# V6_0.net
KiCad netlist of a schematic drawn in EAGLE
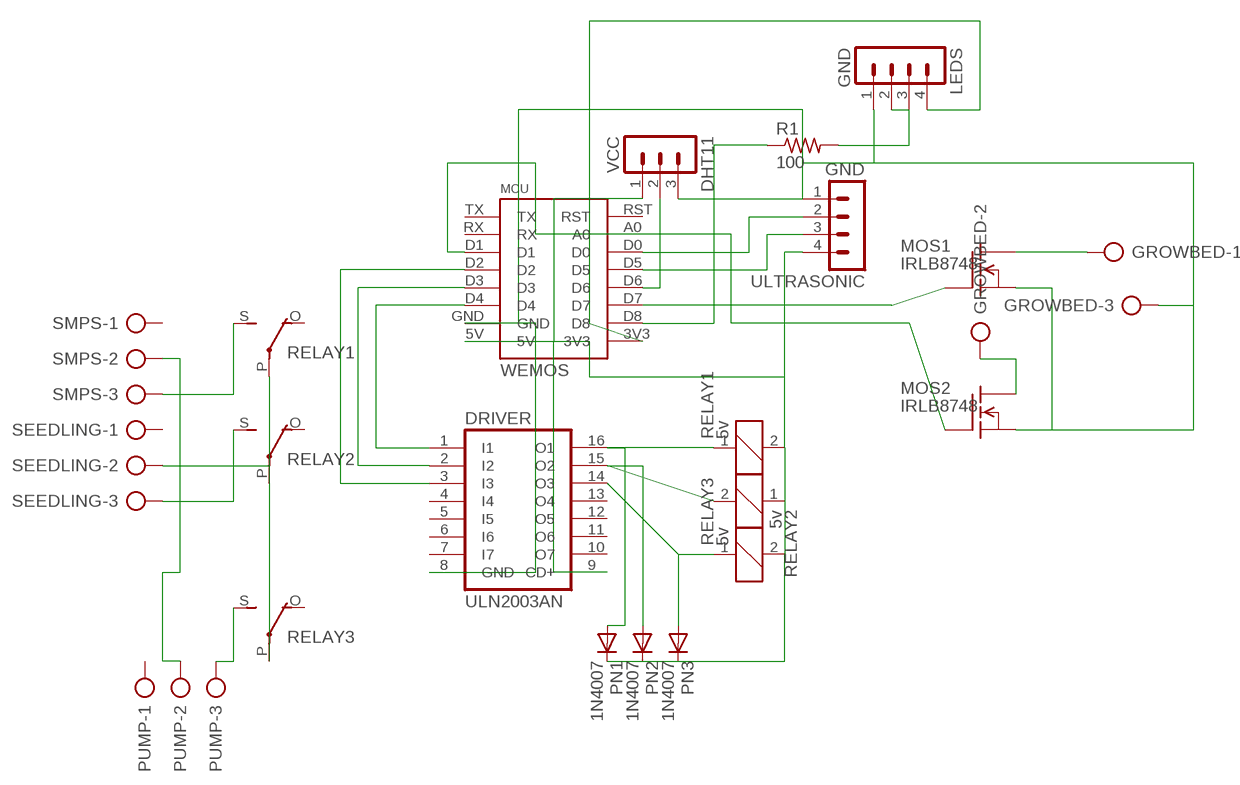
[diagram p0: schematic, sheet 1]

(export (version "E")
  (design (tool "Eeschema 10.0.6"))
  (components
    (comp (ref "DHT11")
      (value "VCC")
      (footprint "eagle-import:MA03-1")
      (libsource (lib "eagle-import") (part "MA03-1"))
    )
    (comp (ref "DRIVER")
      (value "ULN2003AN")
      (footprint "eagle-import:DIL16")
      (libsource (lib "eagle-import") (part "ULN2003AN"))
    )
    (comp (ref "GROWBED")
      (value "AK300/3")
      (footprint "eagle-import:AK300_3")
      (libsource (lib "eagle-import") (part "AK300/3"))
    )
    (comp (ref "LEDS")
      (value "GND")
      (footprint "eagle-import:MA04-1")
      (fields (field (name "OC_FARNELL") "unknown") (field (name "OC_NEWARK") "unknown"))
      (libsource (lib "eagle-import") (part "MA04-1"))
    )
    (comp (ref "MCU")
      (value "WEMOS")
      (footprint "eagle-import:WEMOS")
      (libsource (lib "eagle-import") (part "WEMOS"))
    )
    (comp (ref "MOS1")
      (value "IRLB8748")
      (footprint "eagle-import:TO220")
      (libsource (lib "eagle-import") (part "IRF540"))
    )
    (comp (ref "MOS2")
      (value "IRLB8748")
      (footprint "eagle-import:TO220")
      (libsource (lib "eagle-import") (part "IRF540"))
    )
    (comp (ref "PN1")
      (value "1N4007")
      (footprint "eagle-import:DO41-10")
      (libsource (lib "eagle-import") (part "1N4004"))
    )
    (comp (ref "PN2")
      (value "1N4007")
      (footprint "eagle-import:DO41-10")
      (libsource (lib "eagle-import") (part "1N4004"))
    )
    (comp (ref "PN3")
      (value "1N4007")
      (footprint "eagle-import:DO41-10")
      (libsource (lib "eagle-import") (part "1N4004"))
    )
    (comp (ref "PUMP")
      (value "AK300/3")
      (footprint "eagle-import:AK300_3")
      (libsource (lib "eagle-import") (part "AK300/3"))
    )
    (comp (ref "R1")
      (value "100")
      (footprint "eagle-import:0207_7")
      (libsource (lib "eagle-import") (part "R-US_0207/7"))
    )
    (comp (ref "RELAY1")
      (value "5v")
      (footprint "eagle-import:ZF112")
      (libsource (lib "eagle-import") (part "ZF112"))
    )
    (comp (ref "RELAY2")
      (value "5v")
      (footprint "eagle-import:ZF112")
      (libsource (lib "eagle-import") (part "ZF112"))
    )
    (comp (ref "RELAY3")
      (value "5v")
      (footprint "eagle-import:ZF112")
      (libsource (lib "eagle-import") (part "ZF112"))
    )
    (comp (ref "SEEDLING")
      (value "AK300/3")
      (footprint "eagle-import:AK300_3")
      (libsource (lib "eagle-import") (part "AK300/3"))
    )
    (comp (ref "SMPS")
      (value "AK300/3")
      (footprint "eagle-import:AK300_3")
      (libsource (lib "eagle-import") (part "AK300/3"))
    )
    (comp (ref "ULTRASONIC")
      (value "GND")
      (footprint "eagle-import:MA04-1")
      (libsource (lib "eagle-import") (part "MA04-1"))
    )
  )
  (nets
    (net (code "1") (name "Net-(DHT11-Pad2)") (class "Default")
      (node (ref "DHT11") (pin "2") (pinfunction "2_2") (pintype "passive"))
      (node (ref "MCU") (pin "D6") (pinfunction "D6_D6") (pintype "bidirectional"))
    )
    (net (code "2") (name "Net-(DRIVER-CD+)") (class "Default")
      (node (ref "DHT11") (pin "1") (pinfunction "1_1") (pintype "passive"))
      (node (ref "DRIVER") (pin "9") (pinfunction "CD+_9") (pintype "passive"))
      (node (ref "MCU") (pin "5V") (pinfunction "5V_5V") (pintype "bidirectional"))
      (node (ref "PN1") (pin "C") (pinfunction "C_C") (pintype "passive"))
      (node (ref "PN2") (pin "C") (pinfunction "C_C") (pintype "passive"))
      (node (ref "PN3") (pin "C") (pinfunction "C_C") (pintype "passive"))
      (node (ref "RELAY1") (pin "2") (pinfunction "2_2") (pintype "passive"))
      (node (ref "RELAY2") (pin "1") (pinfunction "1_1") (pintype "passive"))
      (node (ref "RELAY3") (pin "2") (pinfunction "2_2") (pintype "passive"))
      (node (ref "ULTRASONIC") (pin "4") (pinfunction "4_4") (pintype "passive"))
    )
    (net (code "3") (name "Net-(DRIVER-GND)") (class "Default")
      (node (ref "DHT11") (pin "3") (pinfunction "3_3") (pintype "passive"))
      (node (ref "DRIVER") (pin "8") (pinfunction "GND_8") (pintype "power_in"))
      (node (ref "GROWBED") (pin "3") (pinfunction "KL_3") (pintype "passive"))
      (node (ref "LEDS") (pin "1") (pinfunction "1_1") (pintype "passive"))
      (node (ref "MCU") (pin "GND") (pinfunction "GND_GND") (pintype "bidirectional"))
      (node (ref "MOS1") (pin "3") (pinfunction "S_3") (pintype "passive"))
      (node (ref "MOS2") (pin "3") (pinfunction "S_3") (pintype "passive"))
      (node (ref "ULTRASONIC") (pin "1") (pinfunction "1_1") (pintype "passive"))
    )
    (net (code "4") (name "Net-(DRIVER-I1)") (class "Default")
      (node (ref "DRIVER") (pin "1") (pinfunction "I1_1") (pintype "input"))
      (node (ref "MCU") (pin "D4") (pinfunction "D4_D4") (pintype "bidirectional"))
    )
    (net (code "5") (name "Net-(DRIVER-I2)") (class "Default")
      (node (ref "DRIVER") (pin "2") (pinfunction "I2_2") (pintype "input"))
      (node (ref "MCU") (pin "D3") (pinfunction "D3_D3") (pintype "bidirectional"))
    )
    (net (code "6") (name "Net-(DRIVER-I3)") (class "Default")
      (node (ref "DRIVER") (pin "3") (pinfunction "I3_3") (pintype "input"))
      (node (ref "MCU") (pin "D2") (pinfunction "D2_D2") (pintype "bidirectional"))
    )
    (net (code "7") (name "Net-(DRIVER-O1)") (class "Default")
      (node (ref "DRIVER") (pin "16") (pinfunction "O1_16") (pintype "open_collector"))
      (node (ref "PN1") (pin "A") (pinfunction "A_A") (pintype "passive"))
      (node (ref "RELAY1") (pin "1") (pinfunction "1_1") (pintype "passive"))
    )
    (net (code "8") (name "Net-(DRIVER-O2)") (class "Default")
      (node (ref "DRIVER") (pin "15") (pinfunction "O2_15") (pintype "open_collector"))
      (node (ref "PN2") (pin "A") (pinfunction "A_A") (pintype "passive"))
      (node (ref "RELAY2") (pin "2") (pinfunction "2_2") (pintype "passive"))
    )
    (net (code "9") (name "Net-(DRIVER-O3)") (class "Default")
      (node (ref "DRIVER") (pin "14") (pinfunction "O3_14") (pintype "open_collector"))
      (node (ref "PN3") (pin "A") (pinfunction "A_A") (pintype "passive"))
      (node (ref "RELAY3") (pin "1") (pinfunction "1_1") (pintype "passive"))
    )
    (net (code "10") (name "Net-(GROWBEDA-KL)") (class "Default")
      (node (ref "GROWBED") (pin "1") (pinfunction "KL_1") (pintype "passive"))
      (node (ref "MOS1") (pin "2") (pinfunction "D_2") (pintype "passive"))
    )
    (net (code "11") (name "Net-(GROWBEDB-KL)") (class "Default")
      (node (ref "GROWBED") (pin "2") (pinfunction "KL_2") (pintype "passive"))
      (node (ref "MOS2") (pin "2") (pinfunction "D_2") (pintype "passive"))
    )
    (net (code "12") (name "Net-(LEDS-Pad2)") (class "Default")
      (node (ref "LEDS") (pin "2") (pinfunction "2_2") (pintype "passive"))
      (node (ref "LEDS") (pin "3") (pinfunction "3_3") (pintype "passive"))
      (node (ref "R1") (pin "2") (pinfunction "2_2") (pintype "passive"))
    )
    (net (code "13") (name "Net-(LEDS-Pad4)") (class "Default")
      (node (ref "LEDS") (pin "4") (pinfunction "4_4") (pintype "passive"))
      (node (ref "MCU") (pin "3V3") (pinfunction "3V3_3V3") (pintype "bidirectional"))
    )
    (net (code "14") (name "Net-(MCU-PadD0)") (class "Default")
      (node (ref "MCU") (pin "D0") (pinfunction "D0_D0") (pintype "bidirectional"))
      (node (ref "ULTRASONIC") (pin "2") (pinfunction "2_2") (pintype "passive"))
    )
    (net (code "15") (name "Net-(MCU-PadD5)") (class "Default")
      (node (ref "MCU") (pin "D5") (pinfunction "D5_D5") (pintype "bidirectional"))
      (node (ref "ULTRASONIC") (pin "3") (pinfunction "3_3") (pintype "passive"))
    )
    (net (code "16") (name "Net-(MCU-PadD8)") (class "Default")
      (node (ref "MCU") (pin "D8") (pinfunction "D8_D8") (pintype "bidirectional"))
      (node (ref "R1") (pin "1") (pinfunction "1_1") (pintype "passive"))
    )
    (net (code "17") (name "Net-(MOS1-G)") (class "Default")
      (node (ref "MCU") (pin "D7") (pinfunction "D7_D7") (pintype "bidirectional"))
      (node (ref "MOS1") (pin "1") (pinfunction "G_1") (pintype "passive"))
    )
    (net (code "18") (name "Net-(MOS2-G)") (class "Default")
      (node (ref "MCU") (pin "D1") (pinfunction "D1_D1") (pintype "bidirectional"))
      (node (ref "MOS2") (pin "1") (pinfunction "G_1") (pintype "passive"))
    )
    (net (code "19") (name "Net-(PUMPB-KL)") (class "Default")
      (node (ref "PUMP") (pin "2") (pinfunction "KL_2") (pintype "passive"))
      (node (ref "RELAY1") (pin "P") (pinfunction "P_P") (pintype "passive"))
      (node (ref "RELAY2") (pin "P") (pinfunction "P_P") (pintype "passive"))
      (node (ref "RELAY3") (pin "P") (pinfunction "P_P") (pintype "passive"))
      (node (ref "SEEDLING") (pin "2") (pinfunction "KL_2") (pintype "passive"))
      (node (ref "SMPS") (pin "2") (pinfunction "KL_2") (pintype "passive"))
    )
    (net (code "20") (name "Net-(PUMPC-KL)") (class "Default")
      (node (ref "PUMP") (pin "3") (pinfunction "KL_3") (pintype "passive"))
      (node (ref "RELAY3") (pin "S") (pinfunction "S_S") (pintype "passive"))
    )
    (net (code "21") (name "Net-(SEEDLINGC-KL)") (class "Default")
      (node (ref "RELAY2") (pin "S") (pinfunction "S_S") (pintype "passive"))
      (node (ref "SEEDLING") (pin "3") (pinfunction "KL_3") (pintype "passive"))
    )
    (net (code "22") (name "Net-(SMPSC-KL)") (class "Default")
      (node (ref "RELAY1") (pin "S") (pinfunction "S_S") (pintype "passive"))
      (node (ref "SMPS") (pin "3") (pinfunction "KL_3") (pintype "passive"))
    )
    (net (code "23") (name "unconnected-(DRIVER-I4-Pad4)") (class "Default")
      (node (ref "DRIVER") (pin "4") (pinfunction "I4_4") (pintype "input"))
    )
    (net (code "24") (name "unconnected-(DRIVER-I5-Pad5)") (class "Default")
      (node (ref "DRIVER") (pin "5") (pinfunction "I5_5") (pintype "input"))
    )
    (net (code "25") (name "unconnected-(DRIVER-I6-Pad6)") (class "Default")
      (node (ref "DRIVER") (pin "6") (pinfunction "I6_6") (pintype "input"))
    )
    (net (code "26") (name "unconnected-(DRIVER-I7-Pad7)") (class "Default")
      (node (ref "DRIVER") (pin "7") (pinfunction "I7_7") (pintype "input"))
    )
    (net (code "27") (name "unconnected-(DRIVER-O4-Pad13)") (class "Default")
      (node (ref "DRIVER") (pin "13") (pinfunction "O4_13") (pintype "open_collector"))
    )
    (net (code "28") (name "unconnected-(DRIVER-O5-Pad12)") (class "Default")
      (node (ref "DRIVER") (pin "12") (pinfunction "O5_12") (pintype "open_collector"))
    )
    (net (code "29") (name "unconnected-(DRIVER-O6-Pad11)") (class "Default")
      (node (ref "DRIVER") (pin "11") (pinfunction "O6_11") (pintype "open_collector"))
    )
    (net (code "30") (name "unconnected-(DRIVER-O7-Pad10)") (class "Default")
      (node (ref "DRIVER") (pin "10") (pinfunction "O7_10") (pintype "open_collector"))
    )
    (net (code "31") (name "unconnected-(MCU-PadA0)") (class "Default")
      (node (ref "MCU") (pin "A0") (pinfunction "A0_A0") (pintype "bidirectional"))
    )
    (net (code "32") (name "unconnected-(MCU-PadRST)") (class "Default")
      (node (ref "MCU") (pin "RST") (pinfunction "RST_RST") (pintype "bidirectional"))
    )
    (net (code "33") (name "unconnected-(MCU-PadRX)") (class "Default")
      (node (ref "MCU") (pin "RX") (pinfunction "RX_RX") (pintype "bidirectional"))
    )
    (net (code "34") (name "unconnected-(MCU-PadTX)") (class "Default")
      (node (ref "MCU") (pin "TX") (pinfunction "TX_TX") (pintype "bidirectional"))
    )
    (net (code "35") (name "unconnected-(PUMPA-KL-Pad1)") (class "Default")
      (node (ref "PUMP") (pin "1") (pinfunction "KL_1") (pintype "passive"))
    )
    (net (code "36") (name "unconnected-(RELAY1-PadO)") (class "Default")
      (node (ref "RELAY1") (pin "O") (pinfunction "O_O") (pintype "passive"))
    )
    (net (code "37") (name "unconnected-(RELAY2-PadO)") (class "Default")
      (node (ref "RELAY2") (pin "O") (pinfunction "O_O") (pintype "passive"))
    )
    (net (code "38") (name "unconnected-(RELAY3-PadO)") (class "Default")
      (node (ref "RELAY3") (pin "O") (pinfunction "O_O") (pintype "passive"))
    )
    (net (code "39") (name "unconnected-(SEEDLINGA-KL-Pad1)") (class "Default")
      (node (ref "SEEDLING") (pin "1") (pinfunction "KL_1") (pintype "passive"))
    )
    (net (code "40") (name "unconnected-(SMPSA-KL-Pad1)") (class "Default")
      (node (ref "SMPS") (pin "1") (pinfunction "KL_1") (pintype "passive"))
    )
  )
)
